# design.net
KiCad netlist of a schematic drawn in EasyEDA Pro
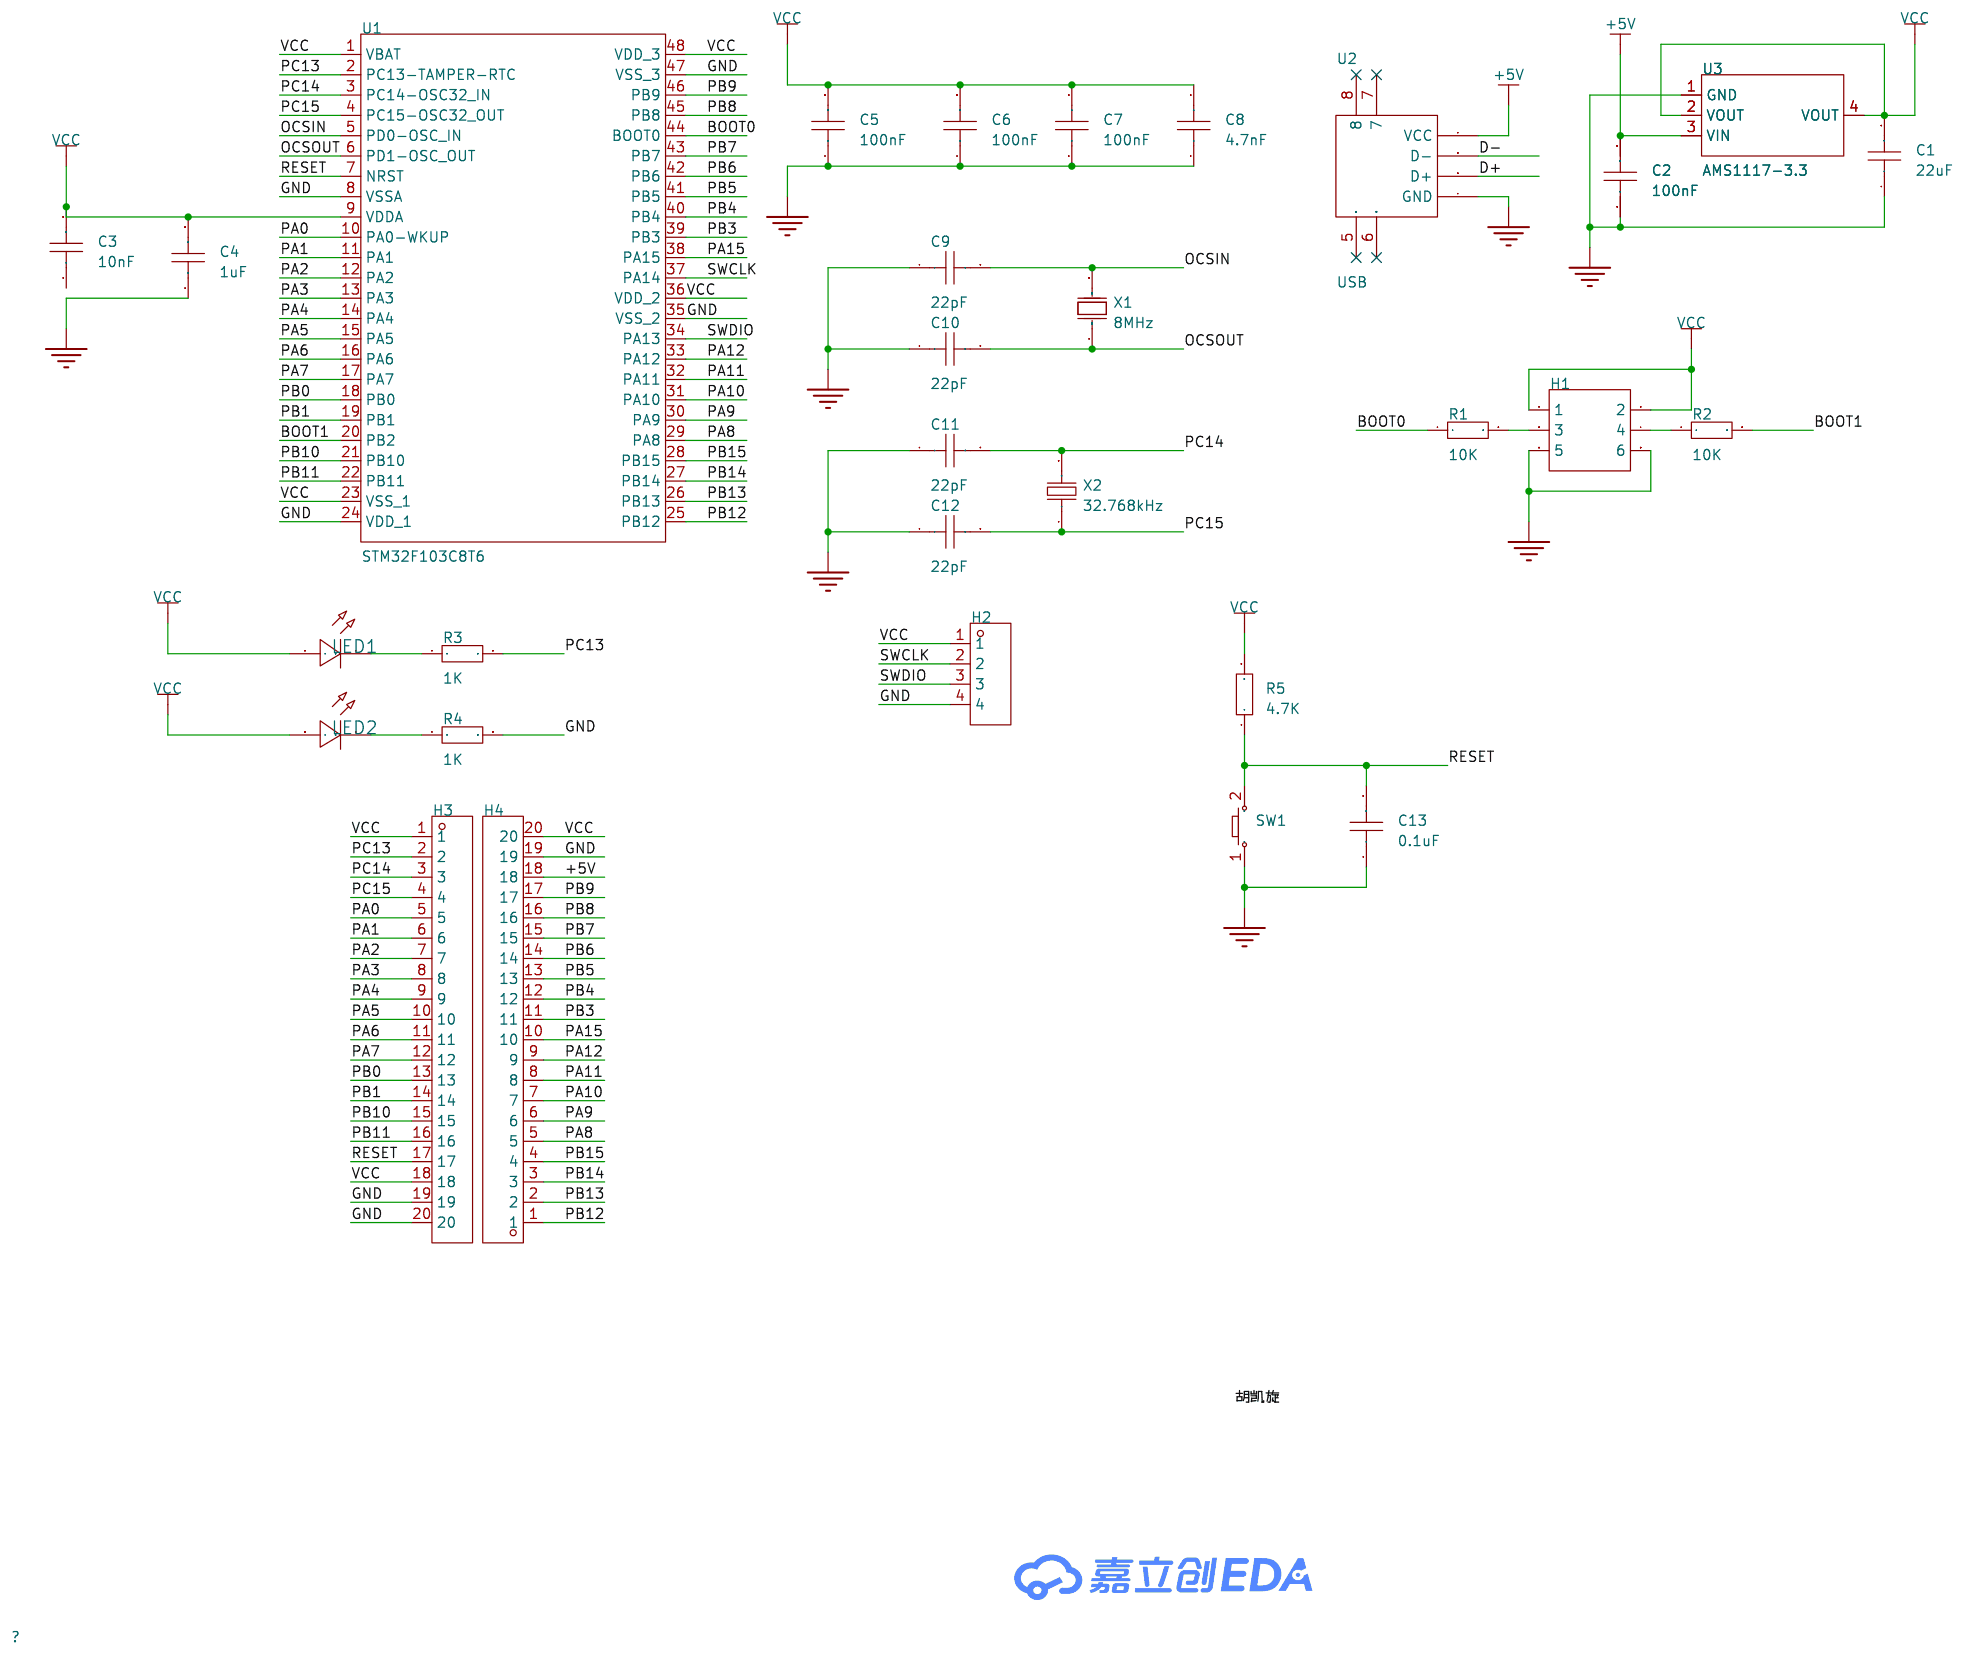
[diagram p0: schematic sheet]

(export (version "E")
  (design (tool "Eeschema 10.0.6"))
  (components
    (comp (ref "C1")
      (value "22uF")
      (footprint "easyedapro:C0603")
      (libsource (lib "easyedapro") (part "CapAcitance"))
    )
    (comp (ref "C2")
      (value "100nF")
      (footprint "easyedapro:C0603")
      (libsource (lib "easyedapro") (part "CapAcitance"))
    )
    (comp (ref "C3")
      (value "10nF")
      (footprint "easyedapro:C0603")
      (libsource (lib "easyedapro") (part "CapAcitance"))
    )
    (comp (ref "C4")
      (value "1uF")
      (footprint "easyedapro:C0603")
      (libsource (lib "easyedapro") (part "CapAcitance"))
    )
    (comp (ref "C5")
      (value "100nF")
      (footprint "easyedapro:C0603")
      (libsource (lib "easyedapro") (part "CapAcitance"))
    )
    (comp (ref "C6")
      (value "100nF")
      (footprint "easyedapro:C0603")
      (libsource (lib "easyedapro") (part "CapAcitance"))
    )
    (comp (ref "C7")
      (value "100nF")
      (footprint "easyedapro:C0603")
      (libsource (lib "easyedapro") (part "CapAcitance"))
    )
    (comp (ref "C8")
      (value "4.7nF")
      (footprint "easyedapro:C0603")
      (libsource (lib "easyedapro") (part "CapAcitance"))
    )
    (comp (ref "C9")
      (value "22pF")
      (footprint "easyedapro:C0603")
      (libsource (lib "easyedapro") (part "CapAcitance"))
    )
    (comp (ref "C10")
      (value "22pF")
      (footprint "easyedapro:C0603")
      (libsource (lib "easyedapro") (part "CapAcitance"))
    )
    (comp (ref "C11")
      (value "22pF")
      (footprint "easyedapro:C0603")
      (libsource (lib "easyedapro") (part "CapAcitance"))
    )
    (comp (ref "C12")
      (value "22pF")
      (footprint "easyedapro:C0603")
      (libsource (lib "easyedapro") (part "CapAcitance"))
    )
    (comp (ref "C13")
      (value "0.1uF")
      (footprint "easyedapro:C0603")
      (libsource (lib "easyedapro") (part "CapAcitance"))
    )
    (comp (ref "H1")
      (value "~")
      (footprint "easyedapro:HDR-TH_6P-P2.54-V-F-R2-C3-S2.54")
      (libsource (lib "easyedapro") (part "HDR-F-2.54_2x3"))
    )
    (comp (ref "H2")
      (value "~")
      (footprint "easyedapro:HDR-TH_4P-P2.54-V-M")
      (libsource (lib "easyedapro") (part "PZ254V-11-04P"))
    )
    (comp (ref "H3")
      (value "~")
      (footprint "easyedapro:HDR-TH_20P-P2.54-V-M-1")
      (libsource (lib "easyedapro") (part "HDR_2.54-1x20P"))
    )
    (comp (ref "H4")
      (value "~")
      (footprint "easyedapro:HDR-TH_20P-P2.54-V-M-1")
      (libsource (lib "easyedapro") (part "HDR_2.54-1x20P"))
    )
    (comp (ref "LED1")
      (value "~")
      (footprint "easyedapro:LED_0603")
      (libsource (lib "easyedapro") (part "LED_R"))
    )
    (comp (ref "LED2")
      (value "~")
      (footprint "easyedapro:LED_0603")
      (libsource (lib "easyedapro") (part "LED_R"))
    )
    (comp (ref "R1") (value "10K") (footprint "easyedapro:R0603") (libsource (lib "easyedapro") (part "电阻")))
    (comp (ref "R2") (value "10K") (footprint "easyedapro:R0603") (libsource (lib "easyedapro") (part "电阻")))
    (comp (ref "R3") (value "1K") (footprint "easyedapro:R0603") (libsource (lib "easyedapro") (part "电阻")))
    (comp (ref "R4") (value "1K") (footprint "easyedapro:R0603") (libsource (lib "easyedapro") (part "电阻")))
    (comp (ref "R5") (value "4.7K") (footprint "easyedapro:R0603") (libsource (lib "easyedapro") (part "电阻")))
    (comp (ref "SW1")
      (value "~")
      (footprint "easyedapro:Key_SMD_3x4x2")
      (libsource (lib "easyedapro") (part "轻触按键x2"))
    )
    (comp (ref "U1")
      (value "STM32F103C8T6")
      (footprint "easyedapro:LQFP-48_L7.0-W7.0-P0.50-LS9.0-BL")
      (description "CPU内核:ARM-M3;CPU最大主频:72MHz;应用领域:-;")
      (fields (field (name "Manufacturer") "ST(意法半导体)"))
      (libsource (lib "easyedapro") (part "STM32F103C8T6"))
    )
    (comp (ref "U2")
      (value "USB")
      (footprint "easyedapro:USB-SMD_USB_1")
      (libsource (lib "easyedapro") (part "USB"))
    )
    (comp (ref "U3")
      (value "AMS1117-3.3")
      (footprint "easyedapro:SOT-223-3_L6.5-W3.4-P2.30-LS7.0-BR")
      (description "输出类型:固定;工作电压:16V;输出电压:3.3V;输出电流:1A;电源纹波抑制比(PSRR):72dB@(120Hz);输出极性:正极;")
      (fields (field (name "Manufacturer") "AMS"))
      (libsource (lib "easyedapro") (part "AMS1117-3.3"))
    )
    (comp (ref "X1")
      (value "8MHz")
      (footprint "easyedapro:CRYSTAL-SMD_L5.0-W3.2")
      (description "晶振类型:贴片晶振;频率:8MHz;常温频差:±10ppm;负载电容:20pF;频率稳定度:±20ppm;")
      (fields (field (name "Manufacturer Part") "X50328MSB2GI") (field (name "Manufacturer") "YXC(扬兴晶振)"))
      (libsource (lib "easyedapro") (part "X50328MSB2GI"))
    )
    (comp (ref "X2")
      (value "32.768kHz")
      (footprint "easyedapro:FC-135R_L3.2-W1.5")
      (description "晶振类型:贴片晶振;频率:32.768kHz;常温频差:±20ppm;负载电容:12.5pF;")
      (fields (field (name "Manufacturer Part") "Q13FC13500004") (field (name "Manufacturer") "EPSON(爱普生)"))
      (libsource (lib "easyedapro") (part "Q13FC1350000400"))
    )
  )
  (nets
    (net (code "1") (name "+5V") (class "Default")
      (node (ref "C2") (pin "2") (pinfunction "2_2") (pintype "input"))
      (node (ref "H4") (pin "18") (pinfunction "18_18") (pintype "input"))
      (node (ref "U2") (pin "1") (pinfunction "VCC_1") (pintype "input"))
      (node (ref "U3") (pin "3") (pinfunction "VIN_3") (pintype "unspecified"))
    )
    (net (code "2") (name "/BOOT0") (class "Default")
      (node (ref "R1") (pin "1") (pinfunction "1_1") (pintype "input"))
      (node (ref "U1") (pin "44") (pinfunction "BOOT0_44") (pintype "unspecified"))
    )
    (net (code "3") (name "/BOOT1") (class "Default")
      (node (ref "R2") (pin "2") (pinfunction "2_2") (pintype "input"))
      (node (ref "U1") (pin "20") (pinfunction "PB2_20") (pintype "unspecified"))
    )
    (net (code "4") (name "/D+") (class "Default")
      (node (ref "U2") (pin "3") (pinfunction "D+_3") (pintype "input"))
    )
    (net (code "5") (name "/D-") (class "Default")
      (node (ref "U2") (pin "2") (pinfunction "D-_2") (pintype "input"))
    )
    (net (code "6") (name "/OCSIN") (class "Default")
      (node (ref "C9") (pin "2") (pinfunction "2_2") (pintype "input"))
      (node (ref "U1") (pin "5") (pinfunction "PD0-OSC_IN_5") (pintype "unspecified"))
      (node (ref "X1") (pin "2") (pinfunction "OSC2_2") (pintype "input"))
    )
    (net (code "7") (name "/OCSOUT") (class "Default")
      (node (ref "C10") (pin "2") (pinfunction "2_2") (pintype "input"))
      (node (ref "U1") (pin "6") (pinfunction "PD1-OSC_OUT_6") (pintype "unspecified"))
      (node (ref "X1") (pin "1") (pinfunction "OSC1_1") (pintype "input"))
    )
    (net (code "8") (name "/PA0") (class "Default")
      (node (ref "H3") (pin "5") (pinfunction "5_5") (pintype "input"))
      (node (ref "U1") (pin "10") (pinfunction "PA0-WKUP_10") (pintype "unspecified"))
    )
    (net (code "9") (name "/PA1") (class "Default")
      (node (ref "H3") (pin "6") (pinfunction "6_6") (pintype "input"))
      (node (ref "U1") (pin "11") (pinfunction "PA1_11") (pintype "unspecified"))
    )
    (net (code "10") (name "/PA2") (class "Default")
      (node (ref "H3") (pin "7") (pinfunction "7_7") (pintype "input"))
      (node (ref "U1") (pin "12") (pinfunction "PA2_12") (pintype "unspecified"))
    )
    (net (code "11") (name "/PA3") (class "Default")
      (node (ref "H3") (pin "8") (pinfunction "8_8") (pintype "input"))
      (node (ref "U1") (pin "13") (pinfunction "PA3_13") (pintype "unspecified"))
    )
    (net (code "12") (name "/PA4") (class "Default")
      (node (ref "H3") (pin "9") (pinfunction "9_9") (pintype "input"))
      (node (ref "U1") (pin "14") (pinfunction "PA4_14") (pintype "unspecified"))
    )
    (net (code "13") (name "/PA5") (class "Default")
      (node (ref "H3") (pin "10") (pinfunction "10_10") (pintype "input"))
      (node (ref "U1") (pin "15") (pinfunction "PA5_15") (pintype "unspecified"))
    )
    (net (code "14") (name "/PA6") (class "Default")
      (node (ref "H3") (pin "11") (pinfunction "11_11") (pintype "input"))
      (node (ref "U1") (pin "16") (pinfunction "PA6_16") (pintype "unspecified"))
    )
    (net (code "15") (name "/PA7") (class "Default")
      (node (ref "H3") (pin "12") (pinfunction "12_12") (pintype "input"))
      (node (ref "U1") (pin "17") (pinfunction "PA7_17") (pintype "unspecified"))
    )
    (net (code "16") (name "/PA8") (class "Default")
      (node (ref "H4") (pin "5") (pinfunction "5_5") (pintype "input"))
      (node (ref "U1") (pin "29") (pinfunction "PA8_29") (pintype "unspecified"))
    )
    (net (code "17") (name "/PA9") (class "Default")
      (node (ref "H4") (pin "6") (pinfunction "6_6") (pintype "input"))
      (node (ref "U1") (pin "30") (pinfunction "PA9_30") (pintype "unspecified"))
    )
    (net (code "18") (name "/PA10") (class "Default")
      (node (ref "H4") (pin "7") (pinfunction "7_7") (pintype "input"))
      (node (ref "U1") (pin "31") (pinfunction "PA10_31") (pintype "unspecified"))
    )
    (net (code "19") (name "/PA11") (class "Default")
      (node (ref "H4") (pin "8") (pinfunction "8_8") (pintype "input"))
      (node (ref "U1") (pin "32") (pinfunction "PA11_32") (pintype "unspecified"))
    )
    (net (code "20") (name "/PA12") (class "Default")
      (node (ref "H4") (pin "9") (pinfunction "9_9") (pintype "input"))
      (node (ref "U1") (pin "33") (pinfunction "PA12_33") (pintype "unspecified"))
    )
    (net (code "21") (name "/PA15") (class "Default")
      (node (ref "H4") (pin "10") (pinfunction "10_10") (pintype "input"))
      (node (ref "U1") (pin "38") (pinfunction "PA15_38") (pintype "unspecified"))
    )
    (net (code "22") (name "/PB0") (class "Default")
      (node (ref "H3") (pin "13") (pinfunction "13_13") (pintype "input"))
      (node (ref "U1") (pin "18") (pinfunction "PB0_18") (pintype "unspecified"))
    )
    (net (code "23") (name "/PB1") (class "Default")
      (node (ref "H3") (pin "14") (pinfunction "14_14") (pintype "input"))
      (node (ref "U1") (pin "19") (pinfunction "PB1_19") (pintype "unspecified"))
    )
    (net (code "24") (name "/PB3") (class "Default")
      (node (ref "H4") (pin "11") (pinfunction "11_11") (pintype "input"))
      (node (ref "U1") (pin "39") (pinfunction "PB3_39") (pintype "unspecified"))
    )
    (net (code "25") (name "/PB4") (class "Default")
      (node (ref "H4") (pin "12") (pinfunction "12_12") (pintype "input"))
      (node (ref "U1") (pin "40") (pinfunction "PB4_40") (pintype "unspecified"))
    )
    (net (code "26") (name "/PB5") (class "Default")
      (node (ref "H4") (pin "13") (pinfunction "13_13") (pintype "input"))
      (node (ref "U1") (pin "41") (pinfunction "PB5_41") (pintype "unspecified"))
    )
    (net (code "27") (name "/PB6") (class "Default")
      (node (ref "H4") (pin "14") (pinfunction "14_14") (pintype "input"))
      (node (ref "U1") (pin "42") (pinfunction "PB6_42") (pintype "unspecified"))
    )
    (net (code "28") (name "/PB7") (class "Default")
      (node (ref "H4") (pin "15") (pinfunction "15_15") (pintype "input"))
      (node (ref "U1") (pin "43") (pinfunction "PB7_43") (pintype "unspecified"))
    )
    (net (code "29") (name "/PB8") (class "Default")
      (node (ref "H4") (pin "16") (pinfunction "16_16") (pintype "input"))
      (node (ref "U1") (pin "45") (pinfunction "PB8_45") (pintype "unspecified"))
    )
    (net (code "30") (name "/PB9") (class "Default")
      (node (ref "H4") (pin "17") (pinfunction "17_17") (pintype "input"))
      (node (ref "U1") (pin "46") (pinfunction "PB9_46") (pintype "unspecified"))
    )
    (net (code "31") (name "/PB10") (class "Default")
      (node (ref "H3") (pin "15") (pinfunction "15_15") (pintype "input"))
      (node (ref "U1") (pin "21") (pinfunction "PB10_21") (pintype "unspecified"))
    )
    (net (code "32") (name "/PB11") (class "Default")
      (node (ref "H3") (pin "16") (pinfunction "16_16") (pintype "input"))
      (node (ref "U1") (pin "22") (pinfunction "PB11_22") (pintype "unspecified"))
    )
    (net (code "33") (name "/PB12") (class "Default")
      (node (ref "H4") (pin "1") (pinfunction "1_1") (pintype "input"))
      (node (ref "U1") (pin "25") (pinfunction "PB12_25") (pintype "unspecified"))
    )
    (net (code "34") (name "/PB13") (class "Default")
      (node (ref "H4") (pin "2") (pinfunction "2_2") (pintype "input"))
      (node (ref "U1") (pin "26") (pinfunction "PB13_26") (pintype "unspecified"))
    )
    (net (code "35") (name "/PB14") (class "Default")
      (node (ref "H4") (pin "3") (pinfunction "3_3") (pintype "input"))
      (node (ref "U1") (pin "27") (pinfunction "PB14_27") (pintype "unspecified"))
    )
    (net (code "36") (name "/PB15") (class "Default")
      (node (ref "H4") (pin "4") (pinfunction "4_4") (pintype "input"))
      (node (ref "U1") (pin "28") (pinfunction "PB15_28") (pintype "unspecified"))
    )
    (net (code "37") (name "/PC13") (class "Default")
      (node (ref "H3") (pin "2") (pinfunction "2_2") (pintype "input"))
      (node (ref "R3") (pin "2") (pinfunction "2_2") (pintype "input"))
      (node (ref "U1") (pin "2") (pinfunction "PC13-TAMPER-RTC_2") (pintype "unspecified"))
    )
    (net (code "38") (name "/PC14") (class "Default")
      (node (ref "C11") (pin "2") (pinfunction "2_2") (pintype "input"))
      (node (ref "H3") (pin "3") (pinfunction "3_3") (pintype "input"))
      (node (ref "U1") (pin "3") (pinfunction "PC14-OSC32_IN_3") (pintype "unspecified"))
      (node (ref "X2") (pin "2") (pinfunction "2_2") (pintype "unspecified"))
    )
    (net (code "39") (name "/PC15") (class "Default")
      (node (ref "C12") (pin "2") (pinfunction "2_2") (pintype "input"))
      (node (ref "H3") (pin "4") (pinfunction "4_4") (pintype "input"))
      (node (ref "U1") (pin "4") (pinfunction "PC15-OSC32_OUT_4") (pintype "unspecified"))
      (node (ref "X2") (pin "1") (pinfunction "1_1") (pintype "unspecified"))
    )
    (net (code "40") (name "/RESET") (class "Default")
      (node (ref "C13") (pin "2") (pinfunction "2_2") (pintype "input"))
      (node (ref "H3") (pin "17") (pinfunction "17_17") (pintype "input"))
      (node (ref "R5") (pin "1") (pinfunction "1_1") (pintype "input"))
      (node (ref "SW1") (pin "2") (pinfunction "2_2") (pintype "input"))
      (node (ref "U1") (pin "7") (pinfunction "NRST_7") (pintype "unspecified"))
    )
    (net (code "41") (name "/SWCLK") (class "Default")
      (node (ref "H2") (pin "2") (pinfunction "2_2") (pintype "unspecified"))
      (node (ref "U1") (pin "37") (pinfunction "PA14_37") (pintype "unspecified"))
    )
    (net (code "42") (name "/SWDIO") (class "Default")
      (node (ref "H2") (pin "3") (pinfunction "3_3") (pintype "unspecified"))
      (node (ref "U1") (pin "34") (pinfunction "PA13_34") (pintype "unspecified"))
    )
    (net (code "43") (name "GND") (class "Default")
      (node (ref "C1") (pin "1") (pinfunction "1_1") (pintype "input"))
      (node (ref "C10") (pin "1") (pinfunction "1_1") (pintype "input"))
      (node (ref "C11") (pin "1") (pinfunction "1_1") (pintype "input"))
      (node (ref "C12") (pin "1") (pinfunction "1_1") (pintype "input"))
      (node (ref "C13") (pin "1") (pinfunction "1_1") (pintype "input"))
      (node (ref "C2") (pin "1") (pinfunction "1_1") (pintype "input"))
      (node (ref "C4") (pin "1") (pinfunction "1_1") (pintype "input"))
      (node (ref "C5") (pin "1") (pinfunction "1_1") (pintype "input"))
      (node (ref "C6") (pin "1") (pinfunction "1_1") (pintype "input"))
      (node (ref "C7") (pin "1") (pinfunction "1_1") (pintype "input"))
      (node (ref "C8") (pin "1") (pinfunction "1_1") (pintype "input"))
      (node (ref "C9") (pin "1") (pinfunction "1_1") (pintype "input"))
      (node (ref "H1") (pin "5") (pinfunction "5_5") (pintype "input"))
      (node (ref "H1") (pin "6") (pinfunction "6_6") (pintype "input"))
      (node (ref "H2") (pin "4") (pinfunction "4_4") (pintype "unspecified"))
      (node (ref "H3") (pin "19") (pinfunction "19_19") (pintype "input"))
      (node (ref "H3") (pin "20") (pinfunction "20_20") (pintype "input"))
      (node (ref "H4") (pin "19") (pinfunction "19_19") (pintype "input"))
      (node (ref "R4") (pin "2") (pinfunction "2_2") (pintype "input"))
      (node (ref "SW1") (pin "1") (pinfunction "1_1") (pintype "input"))
      (node (ref "U1") (pin "24") (pinfunction "VDD_1_24") (pintype "unspecified"))
      (node (ref "U1") (pin "35") (pinfunction "VSS_2_35") (pintype "unspecified"))
      (node (ref "U1") (pin "47") (pinfunction "VSS_3_47") (pintype "unspecified"))
      (node (ref "U1") (pin "8") (pinfunction "VSSA_8") (pintype "unspecified"))
      (node (ref "U2") (pin "4") (pinfunction "GND_4") (pintype "input"))
      (node (ref "U3") (pin "1") (pinfunction "GND_1") (pintype "unspecified"))
    )
    (net (code "44") (name "Net-(H1-Pad3)") (class "Default")
      (node (ref "H1") (pin "3") (pinfunction "3_3") (pintype "input"))
      (node (ref "R1") (pin "2") (pinfunction "2_2") (pintype "input"))
    )
    (net (code "45") (name "Net-(H1-Pad4)") (class "Default")
      (node (ref "H1") (pin "4") (pinfunction "4_4") (pintype "input"))
      (node (ref "R2") (pin "1") (pinfunction "1_1") (pintype "input"))
    )
    (net (code "46") (name "Net-(LED1-C)") (class "Default")
      (node (ref "LED1") (pin "1") (pinfunction "C_1") (pintype "input"))
      (node (ref "R3") (pin "1") (pinfunction "1_1") (pintype "input"))
    )
    (net (code "47") (name "Net-(LED2-C)") (class "Default")
      (node (ref "LED2") (pin "1") (pinfunction "C_1") (pintype "input"))
      (node (ref "R4") (pin "1") (pinfunction "1_1") (pintype "input"))
    )
    (net (code "48") (name "VCC") (class "Default")
      (node (ref "C1") (pin "2") (pinfunction "2_2") (pintype "input"))
      (node (ref "C3") (pin "2") (pinfunction "2_2") (pintype "input"))
      (node (ref "C4") (pin "2") (pinfunction "2_2") (pintype "input"))
      (node (ref "C5") (pin "2") (pinfunction "2_2") (pintype "input"))
      (node (ref "C6") (pin "2") (pinfunction "2_2") (pintype "input"))
      (node (ref "C7") (pin "2") (pinfunction "2_2") (pintype "input"))
      (node (ref "C8") (pin "2") (pinfunction "2_2") (pintype "input"))
      (node (ref "H1") (pin "1") (pinfunction "1_1") (pintype "input"))
      (node (ref "H1") (pin "2") (pinfunction "2_2") (pintype "input"))
      (node (ref "H2") (pin "1") (pinfunction "1_1") (pintype "unspecified"))
      (node (ref "H3") (pin "1") (pinfunction "1_1") (pintype "input"))
      (node (ref "H3") (pin "18") (pinfunction "18_18") (pintype "input"))
      (node (ref "H4") (pin "20") (pinfunction "20_20") (pintype "input"))
      (node (ref "LED1") (pin "2") (pinfunction "A_2") (pintype "input"))
      (node (ref "LED2") (pin "2") (pinfunction "A_2") (pintype "input"))
      (node (ref "R5") (pin "2") (pinfunction "2_2") (pintype "input"))
      (node (ref "U1") (pin "1") (pinfunction "VBAT_1") (pintype "unspecified"))
      (node (ref "U1") (pin "23") (pinfunction "VSS_1_23") (pintype "unspecified"))
      (node (ref "U1") (pin "36") (pinfunction "VDD_2_36") (pintype "unspecified"))
      (node (ref "U1") (pin "48") (pinfunction "VDD_3_48") (pintype "unspecified"))
      (node (ref "U1") (pin "9") (pinfunction "VDDA_9") (pintype "unspecified"))
      (node (ref "U3") (pin "2") (pinfunction "VOUT_2") (pintype "unspecified"))
      (node (ref "U3") (pin "4") (pinfunction "VOUT_4") (pintype "unspecified"))
    )
    (net (code "49") (name "unconnected-(C3-Pad1)") (class "Default")
      (node (ref "C3") (pin "1") (pinfunction "1_1") (pintype "input"))
    )
    (net (code "50") (name "unconnected-(U2-Pad7)") (class "Default")
      (node (ref "U2") (pin "7") (pinfunction "7_7") (pintype "unspecified+no_connect"))
    )
    (net (code "51") (name "unconnected-(U2-Pad8)") (class "Default")
      (node (ref "U2") (pin "8") (pinfunction "8_8") (pintype "unspecified+no_connect"))
    )
    (net (code "52") (name "unconnected-(U2-SH1-Pad5)") (class "Default")
      (node (ref "U2") (pin "5") (pinfunction "SH1_5") (pintype "unspecified+no_connect"))
    )
    (net (code "53") (name "unconnected-(U2-SH2-Pad6)") (class "Default")
      (node (ref "U2") (pin "6") (pinfunction "SH2_6") (pintype "unspecified+no_connect"))
    )
  )
)
